# led.net
KiCad netlist of a schematic drawn in Altium Designer
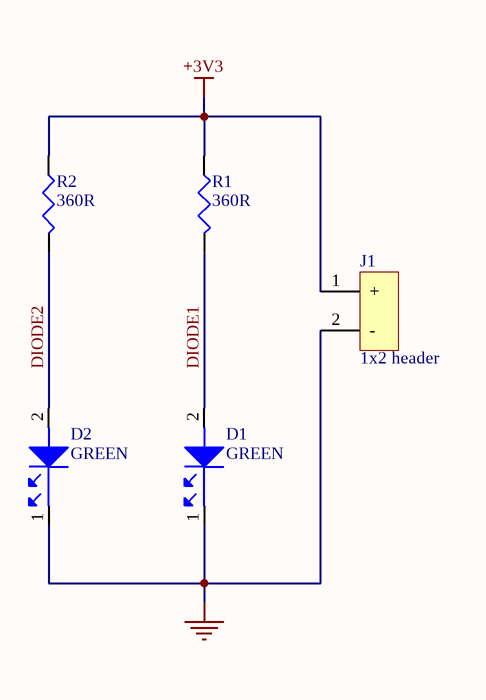
[diagram p0: led.SchDoc]

(export (version "E")
  (design (tool "Eeschema 10.0.6"))
  (components
    (comp (ref "D1")
      (value "GREEN")
      (footprint "LED0603G")
      (description "Single Color LED, Green, Water Clear, 1.15mm")
      (fields
        (field (name "MANUFACTURER") "Vishay Lite-On")
        (field (name "MANUFACTURER PART NUMBER") "LTST-C193KGKT-5A")
      )
      (libsource (lib "led_Schlib") (part "LTST-C193KGKT-5A"))
    )
    (comp (ref "D2")
      (value "GREEN")
      (footprint "LED0603G")
      (description "Single Color LED, Green, Water Clear, 1.15mm")
      (fields
        (field (name "MANUFACTURER") "Vishay Lite-On")
        (field (name "MANUFACTURER PART NUMBER") "LTST-C193KGKT-5A")
      )
      (libsource (lib "led_Schlib") (part "LTST-C193KGKT-5A"))
    )
    (comp (ref "J1")
      (value "1x2 header")
      (footprint "HDR1X2")
      (description "Board Connector, 2 Contact(s), 1 Row(s), Male, Straight, Solder Terminal")
      (fields (field (name "MANUFACTURER") "Molex") (field (name "MANUFACTURER PART NUMBER") "0022292021"))
      (libsource (lib "led_Schlib") (part "0022292021 (2)"))
    )
    (comp (ref "R1")
      (value "360R")
      (footprint "R0805")
      (fields
        (field (name "MANUFACTURER") "Vishay")
        (field (name "MANUFACTURER PART NUMBER") "CRCW0805360RFKEA")
        (field (name "TOLERANCE") "1%")
      )
      (libsource (lib "led_Schlib") (part "CRCW0805360RFKEA"))
    )
    (comp (ref "R2")
      (value "360R")
      (footprint "R0805")
      (fields
        (field (name "MANUFACTURER") "Vishay")
        (field (name "MANUFACTURER PART NUMBER") "CRCW0805360RFKEA")
        (field (name "TOLERANCE") "1%")
      )
      (libsource (lib "led_Schlib") (part "CRCW0805360RFKEA"))
    )
  )
  (nets
    (net (code "1") (name "+3V3") (class "Default")
      (node (ref "J1") (pin "1") (pinfunction "+_1") (pintype "passive"))
      (node (ref "R1") (pin "1") (pinfunction "1_1") (pintype "passive"))
      (node (ref "R2") (pin "1") (pinfunction "1_1") (pintype "passive"))
    )
    (net (code "2") (name "/DIODE1") (class "Default")
      (node (ref "D1") (pin "2") (pinfunction "2_2") (pintype "passive"))
      (node (ref "R1") (pin "2") (pinfunction "2_2") (pintype "passive"))
    )
    (net (code "3") (name "/DIODE2") (class "Default")
      (node (ref "D2") (pin "2") (pinfunction "2_2") (pintype "passive"))
      (node (ref "R2") (pin "2") (pinfunction "2_2") (pintype "passive"))
    )
    (net (code "4") (name "GND") (class "Default")
      (node (ref "D1") (pin "1") (pinfunction "1_1") (pintype "passive"))
      (node (ref "D2") (pin "1") (pinfunction "1_1") (pintype "passive"))
      (node (ref "J1") (pin "2") (pinfunction "-_2") (pintype "passive"))
    )
  )
)
